# Bubble_Display_Controller.net
KiCad netlist of a schematic drawn in EAGLE
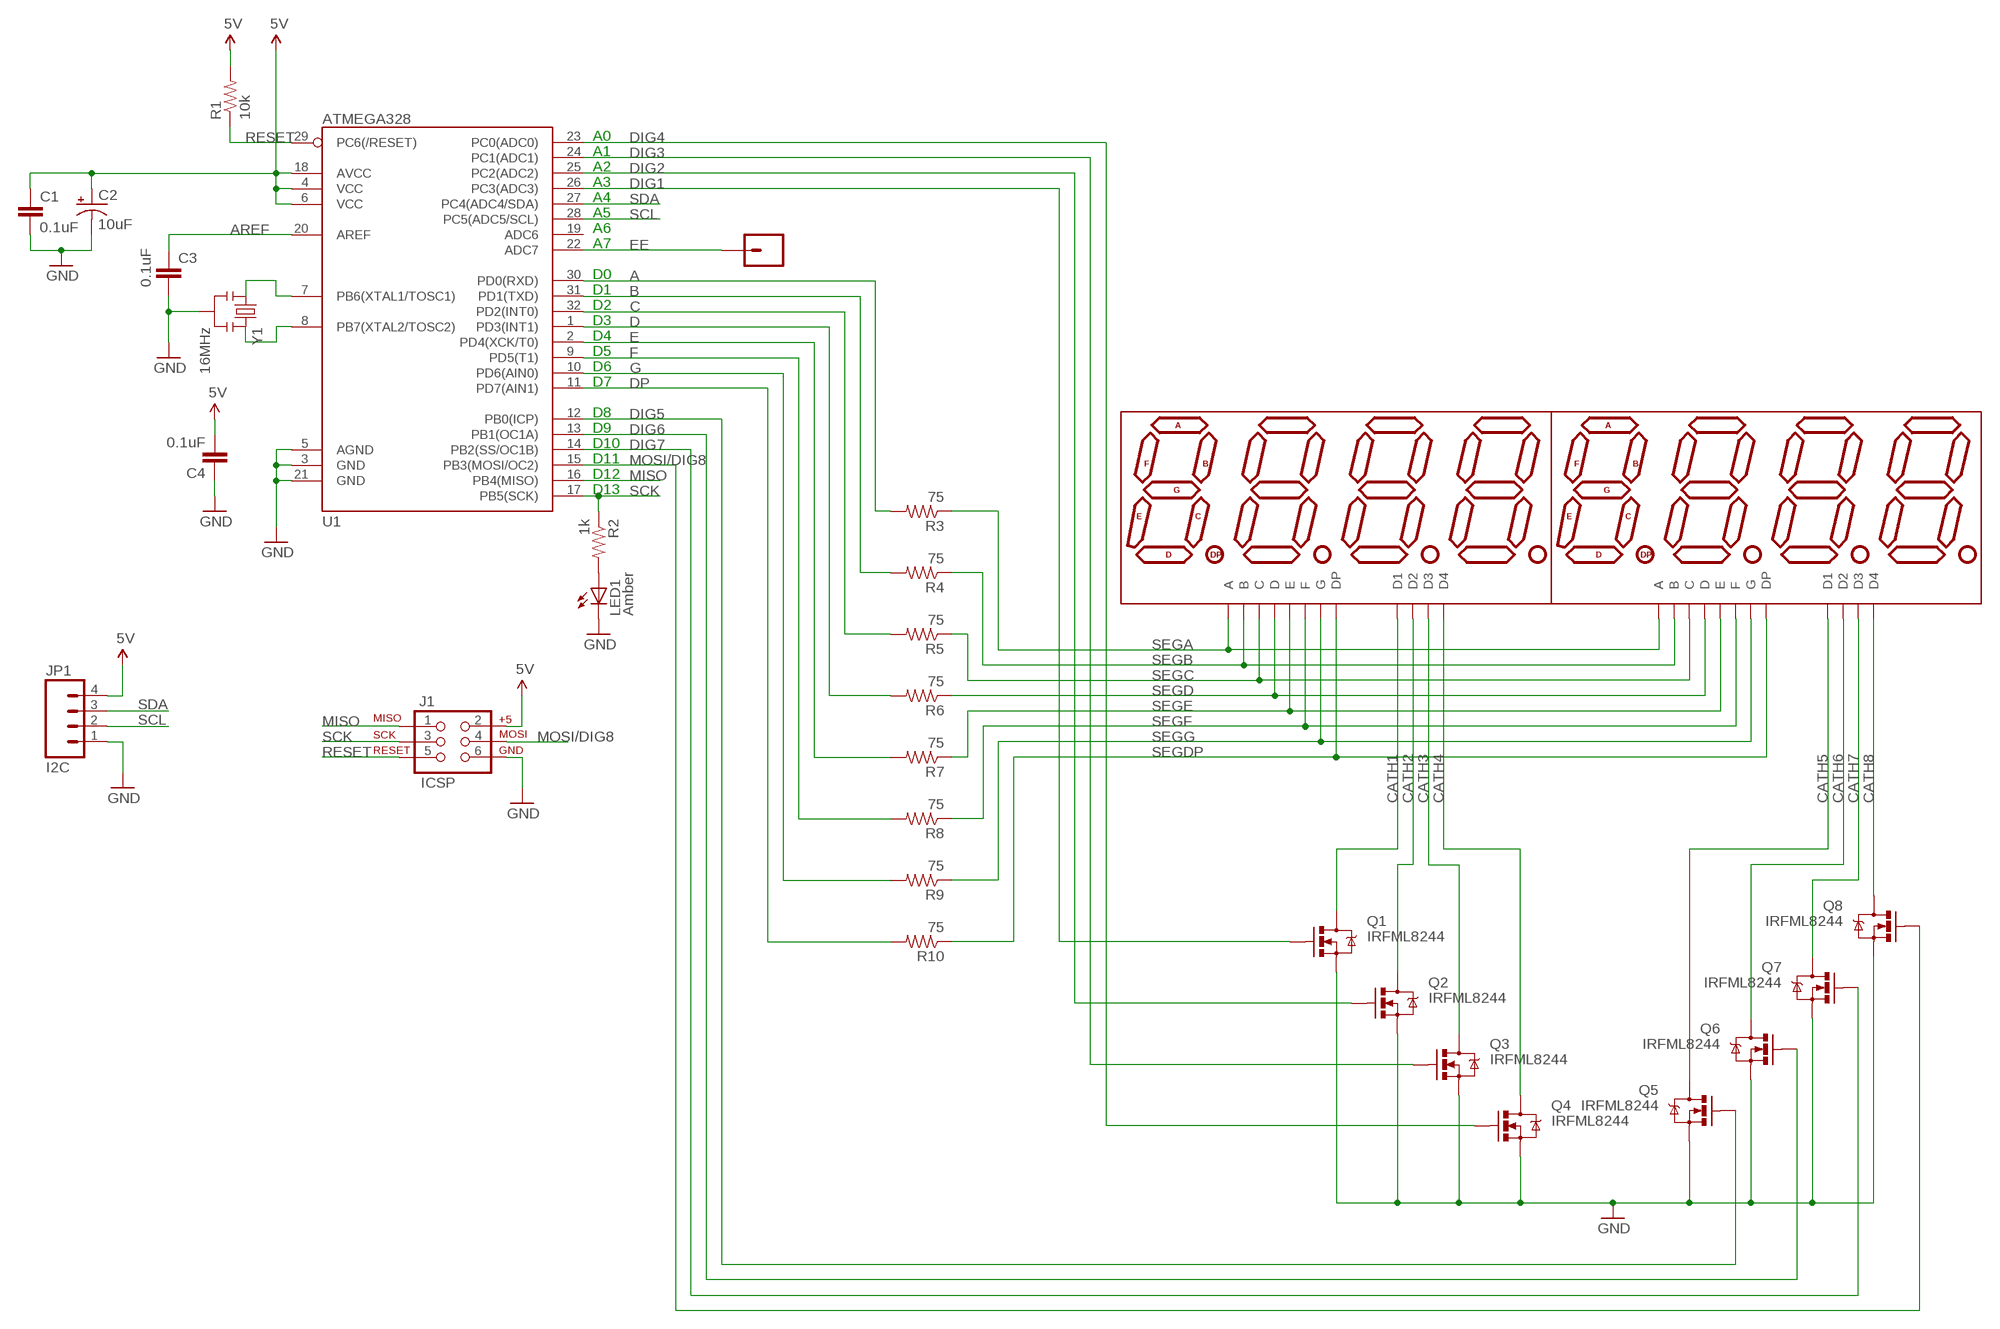
[diagram p0: schematic, sheet 1]

(export (version "E")
  (design (tool "Eeschema 10.0.6"))
  (components
    (comp (ref "C1")
      (value "0.1uF")
      (footprint "eagle-import:0805")
      (libsource (lib "eagle-import") (part "CAP0805"))
    )
    (comp (ref "C2")
      (value "10uF")
      (footprint "eagle-import:0805-POL")
      (libsource (lib "eagle-import") (part "CAP_POL0805"))
    )
    (comp (ref "C3")
      (value "0.1uF")
      (footprint "eagle-import:0805")
      (libsource (lib "eagle-import") (part "CAP0805"))
    )
    (comp (ref "C4")
      (value "0.1uF")
      (footprint "eagle-import:0805")
      (libsource (lib "eagle-import") (part "CAP0805"))
    )
    (comp (ref "DISPLAY1")
      (value "hp")
      (footprint "eagle-import:DIL12")
      (libsource (lib "eagle-import") (part "7-SEGMENT-4DIGIT-COUNTER-HP-BUBBLE"))
    )
    (comp (ref "DISPLAY2")
      (value "hp")
      (footprint "eagle-import:DIL12")
      (libsource (lib "eagle-import") (part "7-SEGMENT-4DIGIT-COUNTER-HP-BUBBLE"))
    )
    (comp (ref "J1")
      (value "ICSP")
      (footprint "eagle-import:2X3")
      (libsource (lib "eagle-import") (part "AVR_SPI_PRG_6PTH"))
    )
    (comp (ref "JP1")
      (value "I2C")
      (footprint "eagle-import:1X04")
      (libsource (lib "eagle-import") (part "M04PTH"))
    )
    (comp (ref "JP2")
      (value "BREADBD_VIA")
      (footprint "eagle-import:BBD-VIA")
      (libsource (lib "eagle-import") (part "BREADBD_VIA"))
    )
    (comp (ref "LED1")
      (value "Amber")
      (footprint "eagle-import:0805-LED")
      (libsource (lib "eagle-import") (part "LED-0805"))
    )
    (comp (ref "Q1")
      (value "IRFML8244")
      (footprint "eagle-import:SOT23")
      (libsource (lib "eagle-import") (part "MOSFET-NCHANNELBSS123LT1G"))
    )
    (comp (ref "Q2")
      (value "IRFML8244")
      (footprint "eagle-import:SOT23")
      (libsource (lib "eagle-import") (part "MOSFET-NCHANNELBSS123LT1G"))
    )
    (comp (ref "Q3")
      (value "IRFML8244")
      (footprint "eagle-import:SOT23")
      (libsource (lib "eagle-import") (part "MOSFET-NCHANNELBSS123LT1G"))
    )
    (comp (ref "Q4")
      (value "IRFML8244")
      (footprint "eagle-import:SOT23")
      (libsource (lib "eagle-import") (part "MOSFET-NCHANNELBSS123LT1G"))
    )
    (comp (ref "Q5")
      (value "IRFML8244")
      (footprint "eagle-import:SOT23")
      (libsource (lib "eagle-import") (part "MOSFET-NCHANNELBSS123LT1G"))
    )
    (comp (ref "Q6")
      (value "IRFML8244")
      (footprint "eagle-import:SOT23")
      (libsource (lib "eagle-import") (part "MOSFET-NCHANNELBSS123LT1G"))
    )
    (comp (ref "Q7")
      (value "IRFML8244")
      (footprint "eagle-import:SOT23")
      (libsource (lib "eagle-import") (part "MOSFET-NCHANNELBSS123LT1G"))
    )
    (comp (ref "Q8")
      (value "IRFML8244")
      (footprint "eagle-import:SOT23")
      (libsource (lib "eagle-import") (part "MOSFET-NCHANNELBSS123LT1G"))
    )
    (comp (ref "R1")
      (value "10k")
      (footprint "eagle-import:0805")
      (libsource (lib "eagle-import") (part "RESISTOR0805-RES"))
    )
    (comp (ref "R2")
      (value "1k")
      (footprint "eagle-import:0805")
      (libsource (lib "eagle-import") (part "RESISTOR0805-RES"))
    )
    (comp (ref "R3")
      (value "75")
      (footprint "eagle-import:0805")
      (libsource (lib "eagle-import") (part "RESISTOR0805-RES"))
    )
    (comp (ref "R4")
      (value "75")
      (footprint "eagle-import:0805")
      (libsource (lib "eagle-import") (part "RESISTOR0805-RES"))
    )
    (comp (ref "R5")
      (value "75")
      (footprint "eagle-import:0805")
      (libsource (lib "eagle-import") (part "RESISTOR0805-RES"))
    )
    (comp (ref "R6")
      (value "75")
      (footprint "eagle-import:0805")
      (libsource (lib "eagle-import") (part "RESISTOR0805-RES"))
    )
    (comp (ref "R7")
      (value "75")
      (footprint "eagle-import:0805")
      (libsource (lib "eagle-import") (part "RESISTOR0805-RES"))
    )
    (comp (ref "R8")
      (value "75")
      (footprint "eagle-import:0805")
      (libsource (lib "eagle-import") (part "RESISTOR0805-RES"))
    )
    (comp (ref "R9")
      (value "75")
      (footprint "eagle-import:0805")
      (libsource (lib "eagle-import") (part "RESISTOR0805-RES"))
    )
    (comp (ref "R10")
      (value "75")
      (footprint "eagle-import:0805")
      (libsource (lib "eagle-import") (part "RESISTOR0805-RES"))
    )
    (comp (ref "U1")
      (value "ATMEGA328")
      (footprint "eagle-import:TQFP32-08")
      (libsource (lib "eagle-import") (part "ATMEGA168"))
    )
    (comp (ref "Y1")
      (value "16MHz")
      (footprint "eagle-import:RESONATOR-SMD")
      (libsource (lib "eagle-import") (part "RESONATORSMD"))
    )
  )
  (nets
    (net (code "1") (name "/A") (class "Default")
      (node (ref "R3") (pin "2") (pinfunction "2_2") (pintype "passive"))
      (node (ref "U1") (pin "30") (pinfunction "PD0(RXD)_30") (pintype "bidirectional"))
    )
    (net (code "2") (name "/AREF") (class "Default")
      (node (ref "C3") (pin "1") (pinfunction "1_1") (pintype "passive"))
      (node (ref "U1") (pin "20") (pinfunction "AREF_20") (pintype "bidirectional"))
    )
    (net (code "3") (name "/B") (class "Default")
      (node (ref "R4") (pin "2") (pinfunction "2_2") (pintype "passive"))
      (node (ref "U1") (pin "31") (pinfunction "PD1(TXD)_31") (pintype "bidirectional"))
    )
    (net (code "4") (name "/C") (class "Default")
      (node (ref "R5") (pin "2") (pinfunction "2_2") (pintype "passive"))
      (node (ref "U1") (pin "32") (pinfunction "PD2(INT0)_32") (pintype "bidirectional"))
    )
    (net (code "5") (name "/CATH1") (class "Default")
      (node (ref "DISPLAY1") (pin "1") (pinfunction "D1_1") (pintype "bidirectional"))
      (node (ref "Q1") (pin "3") (pinfunction "D_3") (pintype "passive"))
    )
    (net (code "6") (name "/CATH2") (class "Default")
      (node (ref "DISPLAY1") (pin "10") (pinfunction "D2_10") (pintype "bidirectional"))
      (node (ref "Q2") (pin "3") (pinfunction "D_3") (pintype "passive"))
    )
    (net (code "7") (name "/CATH3") (class "Default")
      (node (ref "DISPLAY1") (pin "4") (pinfunction "D3_4") (pintype "bidirectional"))
      (node (ref "Q3") (pin "3") (pinfunction "D_3") (pintype "passive"))
    )
    (net (code "8") (name "/CATH4") (class "Default")
      (node (ref "DISPLAY1") (pin "6") (pinfunction "D4_6") (pintype "bidirectional"))
      (node (ref "Q4") (pin "3") (pinfunction "D_3") (pintype "passive"))
    )
    (net (code "9") (name "/CATH5") (class "Default")
      (node (ref "DISPLAY2") (pin "1") (pinfunction "D1_1") (pintype "bidirectional"))
      (node (ref "Q5") (pin "3") (pinfunction "D_3") (pintype "passive"))
    )
    (net (code "10") (name "/CATH6") (class "Default")
      (node (ref "DISPLAY2") (pin "10") (pinfunction "D2_10") (pintype "bidirectional"))
      (node (ref "Q6") (pin "3") (pinfunction "D_3") (pintype "passive"))
    )
    (net (code "11") (name "/CATH7") (class "Default")
      (node (ref "DISPLAY2") (pin "4") (pinfunction "D3_4") (pintype "bidirectional"))
      (node (ref "Q7") (pin "3") (pinfunction "D_3") (pintype "passive"))
    )
    (net (code "12") (name "/CATH8") (class "Default")
      (node (ref "DISPLAY2") (pin "6") (pinfunction "D4_6") (pintype "bidirectional"))
      (node (ref "Q8") (pin "3") (pinfunction "D_3") (pintype "passive"))
    )
    (net (code "13") (name "/D") (class "Default")
      (node (ref "R6") (pin "2") (pinfunction "2_2") (pintype "passive"))
      (node (ref "U1") (pin "1") (pinfunction "PD3(INT1)_1") (pintype "bidirectional"))
    )
    (net (code "14") (name "/DIG1") (class "Default")
      (node (ref "Q1") (pin "1") (pinfunction "G_1") (pintype "passive"))
      (node (ref "U1") (pin "26") (pinfunction "PC3(ADC3)_26") (pintype "bidirectional"))
    )
    (net (code "15") (name "/DIG2") (class "Default")
      (node (ref "Q2") (pin "1") (pinfunction "G_1") (pintype "passive"))
      (node (ref "U1") (pin "25") (pinfunction "PC2(ADC2)_25") (pintype "bidirectional"))
    )
    (net (code "16") (name "/DIG3") (class "Default")
      (node (ref "Q3") (pin "1") (pinfunction "G_1") (pintype "passive"))
      (node (ref "U1") (pin "24") (pinfunction "PC1(ADC1)_24") (pintype "bidirectional"))
    )
    (net (code "17") (name "/DIG4") (class "Default")
      (node (ref "Q4") (pin "1") (pinfunction "G_1") (pintype "passive"))
      (node (ref "U1") (pin "23") (pinfunction "PC0(ADC0)_23") (pintype "bidirectional"))
    )
    (net (code "18") (name "/DIG5") (class "Default")
      (node (ref "Q5") (pin "1") (pinfunction "G_1") (pintype "passive"))
      (node (ref "U1") (pin "12") (pinfunction "PB0(ICP)_12") (pintype "bidirectional"))
    )
    (net (code "19") (name "/DIG6") (class "Default")
      (node (ref "Q6") (pin "1") (pinfunction "G_1") (pintype "passive"))
      (node (ref "U1") (pin "13") (pinfunction "PB1(OC1A)_13") (pintype "bidirectional"))
    )
    (net (code "20") (name "/DIG7") (class "Default")
      (node (ref "Q7") (pin "1") (pinfunction "G_1") (pintype "passive"))
      (node (ref "U1") (pin "14") (pinfunction "PB2(SS/OC1B)_14") (pintype "bidirectional"))
    )
    (net (code "21") (name "/DP") (class "Default")
      (node (ref "R10") (pin "2") (pinfunction "2_2") (pintype "passive"))
      (node (ref "U1") (pin "11") (pinfunction "PD7(AIN1)_11") (pintype "bidirectional"))
    )
    (net (code "22") (name "/E") (class "Default")
      (node (ref "R7") (pin "2") (pinfunction "2_2") (pintype "passive"))
      (node (ref "U1") (pin "2") (pinfunction "PD4(XCK/T0)_2") (pintype "bidirectional"))
    )
    (net (code "23") (name "/EE") (class "Default")
      (node (ref "JP2") (pin "P$1") (pinfunction "1_P$1") (pintype "passive"))
      (node (ref "U1") (pin "22") (pinfunction "ADC7_22") (pintype "bidirectional"))
    )
    (net (code "24") (name "/F") (class "Default")
      (node (ref "R8") (pin "2") (pinfunction "2_2") (pintype "passive"))
      (node (ref "U1") (pin "9") (pinfunction "PD5(T1)_9") (pintype "bidirectional"))
    )
    (net (code "25") (name "/G") (class "Default")
      (node (ref "R9") (pin "2") (pinfunction "2_2") (pintype "passive"))
      (node (ref "U1") (pin "10") (pinfunction "PD6(AIN0)_10") (pintype "bidirectional"))
    )
    (net (code "26") (name "/MISO") (class "Default")
      (node (ref "J1") (pin "1") (pinfunction "1_1") (pintype "passive"))
      (node (ref "U1") (pin "16") (pinfunction "PB4(MISO)_16") (pintype "bidirectional"))
    )
    (net (code "27") (name "/MOSI{slash}DIG8") (class "Default")
      (node (ref "J1") (pin "4") (pinfunction "4_4") (pintype "passive"))
      (node (ref "Q8") (pin "1") (pinfunction "G_1") (pintype "passive"))
      (node (ref "U1") (pin "15") (pinfunction "PB3(MOSI/OC2)_15") (pintype "bidirectional"))
    )
    (net (code "28") (name "/RESET") (class "Default")
      (node (ref "J1") (pin "5") (pinfunction "5_5") (pintype "passive"))
      (node (ref "R1") (pin "1") (pinfunction "1_1") (pintype "passive"))
      (node (ref "U1") (pin "29") (pinfunction "PC6(/RESET)_29") (pintype "bidirectional"))
    )
    (net (code "29") (name "/SCK") (class "Default")
      (node (ref "J1") (pin "3") (pinfunction "3_3") (pintype "passive"))
      (node (ref "R2") (pin "1") (pinfunction "1_1") (pintype "passive"))
      (node (ref "U1") (pin "17") (pinfunction "PB5(SCK)_17") (pintype "bidirectional"))
    )
    (net (code "30") (name "/SCL") (class "Default")
      (node (ref "JP1") (pin "2") (pinfunction "2_2") (pintype "passive"))
      (node (ref "U1") (pin "28") (pinfunction "PC5(ADC5/SCL)_28") (pintype "bidirectional"))
    )
    (net (code "31") (name "/SDA") (class "Default")
      (node (ref "JP1") (pin "3") (pinfunction "3_3") (pintype "passive"))
      (node (ref "U1") (pin "27") (pinfunction "PC4(ADC4/SDA)_27") (pintype "bidirectional"))
    )
    (net (code "32") (name "/SEGA") (class "Default")
      (node (ref "DISPLAY1") (pin "12") (pinfunction "A_12") (pintype "bidirectional"))
      (node (ref "DISPLAY2") (pin "12") (pinfunction "A_12") (pintype "bidirectional"))
      (node (ref "R3") (pin "1") (pinfunction "1_1") (pintype "passive"))
    )
    (net (code "33") (name "/SEGB") (class "Default")
      (node (ref "DISPLAY1") (pin "11") (pinfunction "B_11") (pintype "bidirectional"))
      (node (ref "DISPLAY2") (pin "11") (pinfunction "B_11") (pintype "bidirectional"))
      (node (ref "R4") (pin "1") (pinfunction "1_1") (pintype "passive"))
    )
    (net (code "34") (name "/SEGC") (class "Default")
      (node (ref "DISPLAY1") (pin "3") (pinfunction "C_3") (pintype "bidirectional"))
      (node (ref "DISPLAY2") (pin "3") (pinfunction "C_3") (pintype "bidirectional"))
      (node (ref "R5") (pin "1") (pinfunction "1_1") (pintype "passive"))
    )
    (net (code "35") (name "/SEGD") (class "Default")
      (node (ref "DISPLAY1") (pin "8") (pinfunction "D_8") (pintype "bidirectional"))
      (node (ref "DISPLAY2") (pin "8") (pinfunction "D_8") (pintype "bidirectional"))
      (node (ref "R6") (pin "1") (pinfunction "1_1") (pintype "passive"))
    )
    (net (code "36") (name "/SEGDP") (class "Default")
      (node (ref "DISPLAY1") (pin "5") (pinfunction "DP_5") (pintype "bidirectional"))
      (node (ref "DISPLAY2") (pin "5") (pinfunction "DP_5") (pintype "bidirectional"))
      (node (ref "R10") (pin "1") (pinfunction "1_1") (pintype "passive"))
    )
    (net (code "37") (name "/SEGE") (class "Default")
      (node (ref "DISPLAY1") (pin "2") (pinfunction "E_2") (pintype "bidirectional"))
      (node (ref "DISPLAY2") (pin "2") (pinfunction "E_2") (pintype "bidirectional"))
      (node (ref "R7") (pin "1") (pinfunction "1_1") (pintype "passive"))
    )
    (net (code "38") (name "/SEGF") (class "Default")
      (node (ref "DISPLAY1") (pin "9") (pinfunction "F_9") (pintype "bidirectional"))
      (node (ref "DISPLAY2") (pin "9") (pinfunction "F_9") (pintype "bidirectional"))
      (node (ref "R8") (pin "1") (pinfunction "1_1") (pintype "passive"))
    )
    (net (code "39") (name "/SEGG") (class "Default")
      (node (ref "DISPLAY1") (pin "7") (pinfunction "G_7") (pintype "bidirectional"))
      (node (ref "DISPLAY2") (pin "7") (pinfunction "G_7") (pintype "bidirectional"))
      (node (ref "R9") (pin "1") (pinfunction "1_1") (pintype "passive"))
    )
    (net (code "40") (name "5V") (class "Default")
      (node (ref "C1") (pin "1") (pinfunction "1_1") (pintype "passive"))
      (node (ref "C2") (pin "1") (pinfunction "+_1") (pintype "passive"))
      (node (ref "C4") (pin "2") (pinfunction "2_2") (pintype "passive"))
      (node (ref "J1") (pin "2") (pinfunction "2_2") (pintype "passive"))
      (node (ref "JP1") (pin "4") (pinfunction "4_4") (pintype "passive"))
      (node (ref "R1") (pin "2") (pinfunction "2_2") (pintype "passive"))
      (node (ref "U1") (pin "18") (pinfunction "AVCC_18") (pintype "bidirectional"))
      (node (ref "U1") (pin "4") (pinfunction "VCC_4") (pintype "bidirectional"))
      (node (ref "U1") (pin "6") (pinfunction "VCC_6") (pintype "bidirectional"))
    )
    (net (code "41") (name "GND") (class "Default")
      (node (ref "C1") (pin "2") (pinfunction "2_2") (pintype "passive"))
      (node (ref "C2") (pin "2") (pinfunction "-_2") (pintype "passive"))
      (node (ref "C3") (pin "2") (pinfunction "2_2") (pintype "passive"))
      (node (ref "C4") (pin "1") (pinfunction "1_1") (pintype "passive"))
      (node (ref "J1") (pin "6") (pinfunction "6_6") (pintype "passive"))
      (node (ref "JP1") (pin "1") (pinfunction "1_1") (pintype "passive"))
      (node (ref "LED1") (pin "C") (pinfunction "C_C") (pintype "passive"))
      (node (ref "Q1") (pin "2") (pinfunction "S_2") (pintype "passive"))
      (node (ref "Q2") (pin "2") (pinfunction "S_2") (pintype "passive"))
      (node (ref "Q3") (pin "2") (pinfunction "S_2") (pintype "passive"))
      (node (ref "Q4") (pin "2") (pinfunction "S_2") (pintype "passive"))
      (node (ref "Q5") (pin "2") (pinfunction "S_2") (pintype "passive"))
      (node (ref "Q6") (pin "2") (pinfunction "S_2") (pintype "passive"))
      (node (ref "Q7") (pin "2") (pinfunction "S_2") (pintype "passive"))
      (node (ref "Q8") (pin "2") (pinfunction "S_2") (pintype "passive"))
      (node (ref "U1") (pin "21") (pinfunction "GND_21") (pintype "bidirectional"))
      (node (ref "U1") (pin "3") (pinfunction "GND_3") (pintype "bidirectional"))
      (node (ref "U1") (pin "5") (pinfunction "AGND_5") (pintype "bidirectional"))
      (node (ref "Y1") (pin "2") (pinfunction "2_2") (pintype "passive"))
    )
    (net (code "42") (name "Net-(LED1-PadA)") (class "Default")
      (node (ref "LED1") (pin "A") (pinfunction "A_A") (pintype "passive"))
      (node (ref "R2") (pin "2") (pinfunction "2_2") (pintype "passive"))
    )
    (net (code "43") (name "Net-(U1-PB6(XTAL1{slash}TOSC1))") (class "Default")
      (node (ref "U1") (pin "7") (pinfunction "PB6(XTAL1/TOSC1)_7") (pintype "bidirectional"))
      (node (ref "Y1") (pin "1") (pinfunction "1_1") (pintype "passive"))
    )
    (net (code "44") (name "Net-(U1-PB7(XTAL2{slash}TOSC2))") (class "Default")
      (node (ref "U1") (pin "8") (pinfunction "PB7(XTAL2/TOSC2)_8") (pintype "bidirectional"))
      (node (ref "Y1") (pin "3") (pinfunction "3_3") (pintype "passive"))
    )
    (net (code "45") (name "unconnected-(U1-ADC6-Pad19)") (class "Default")
      (node (ref "U1") (pin "19") (pinfunction "ADC6_19") (pintype "bidirectional"))
    )
  )
)
